# P25_DI_DO.net
KiCad netlist of a schematic drawn in Altium Designer
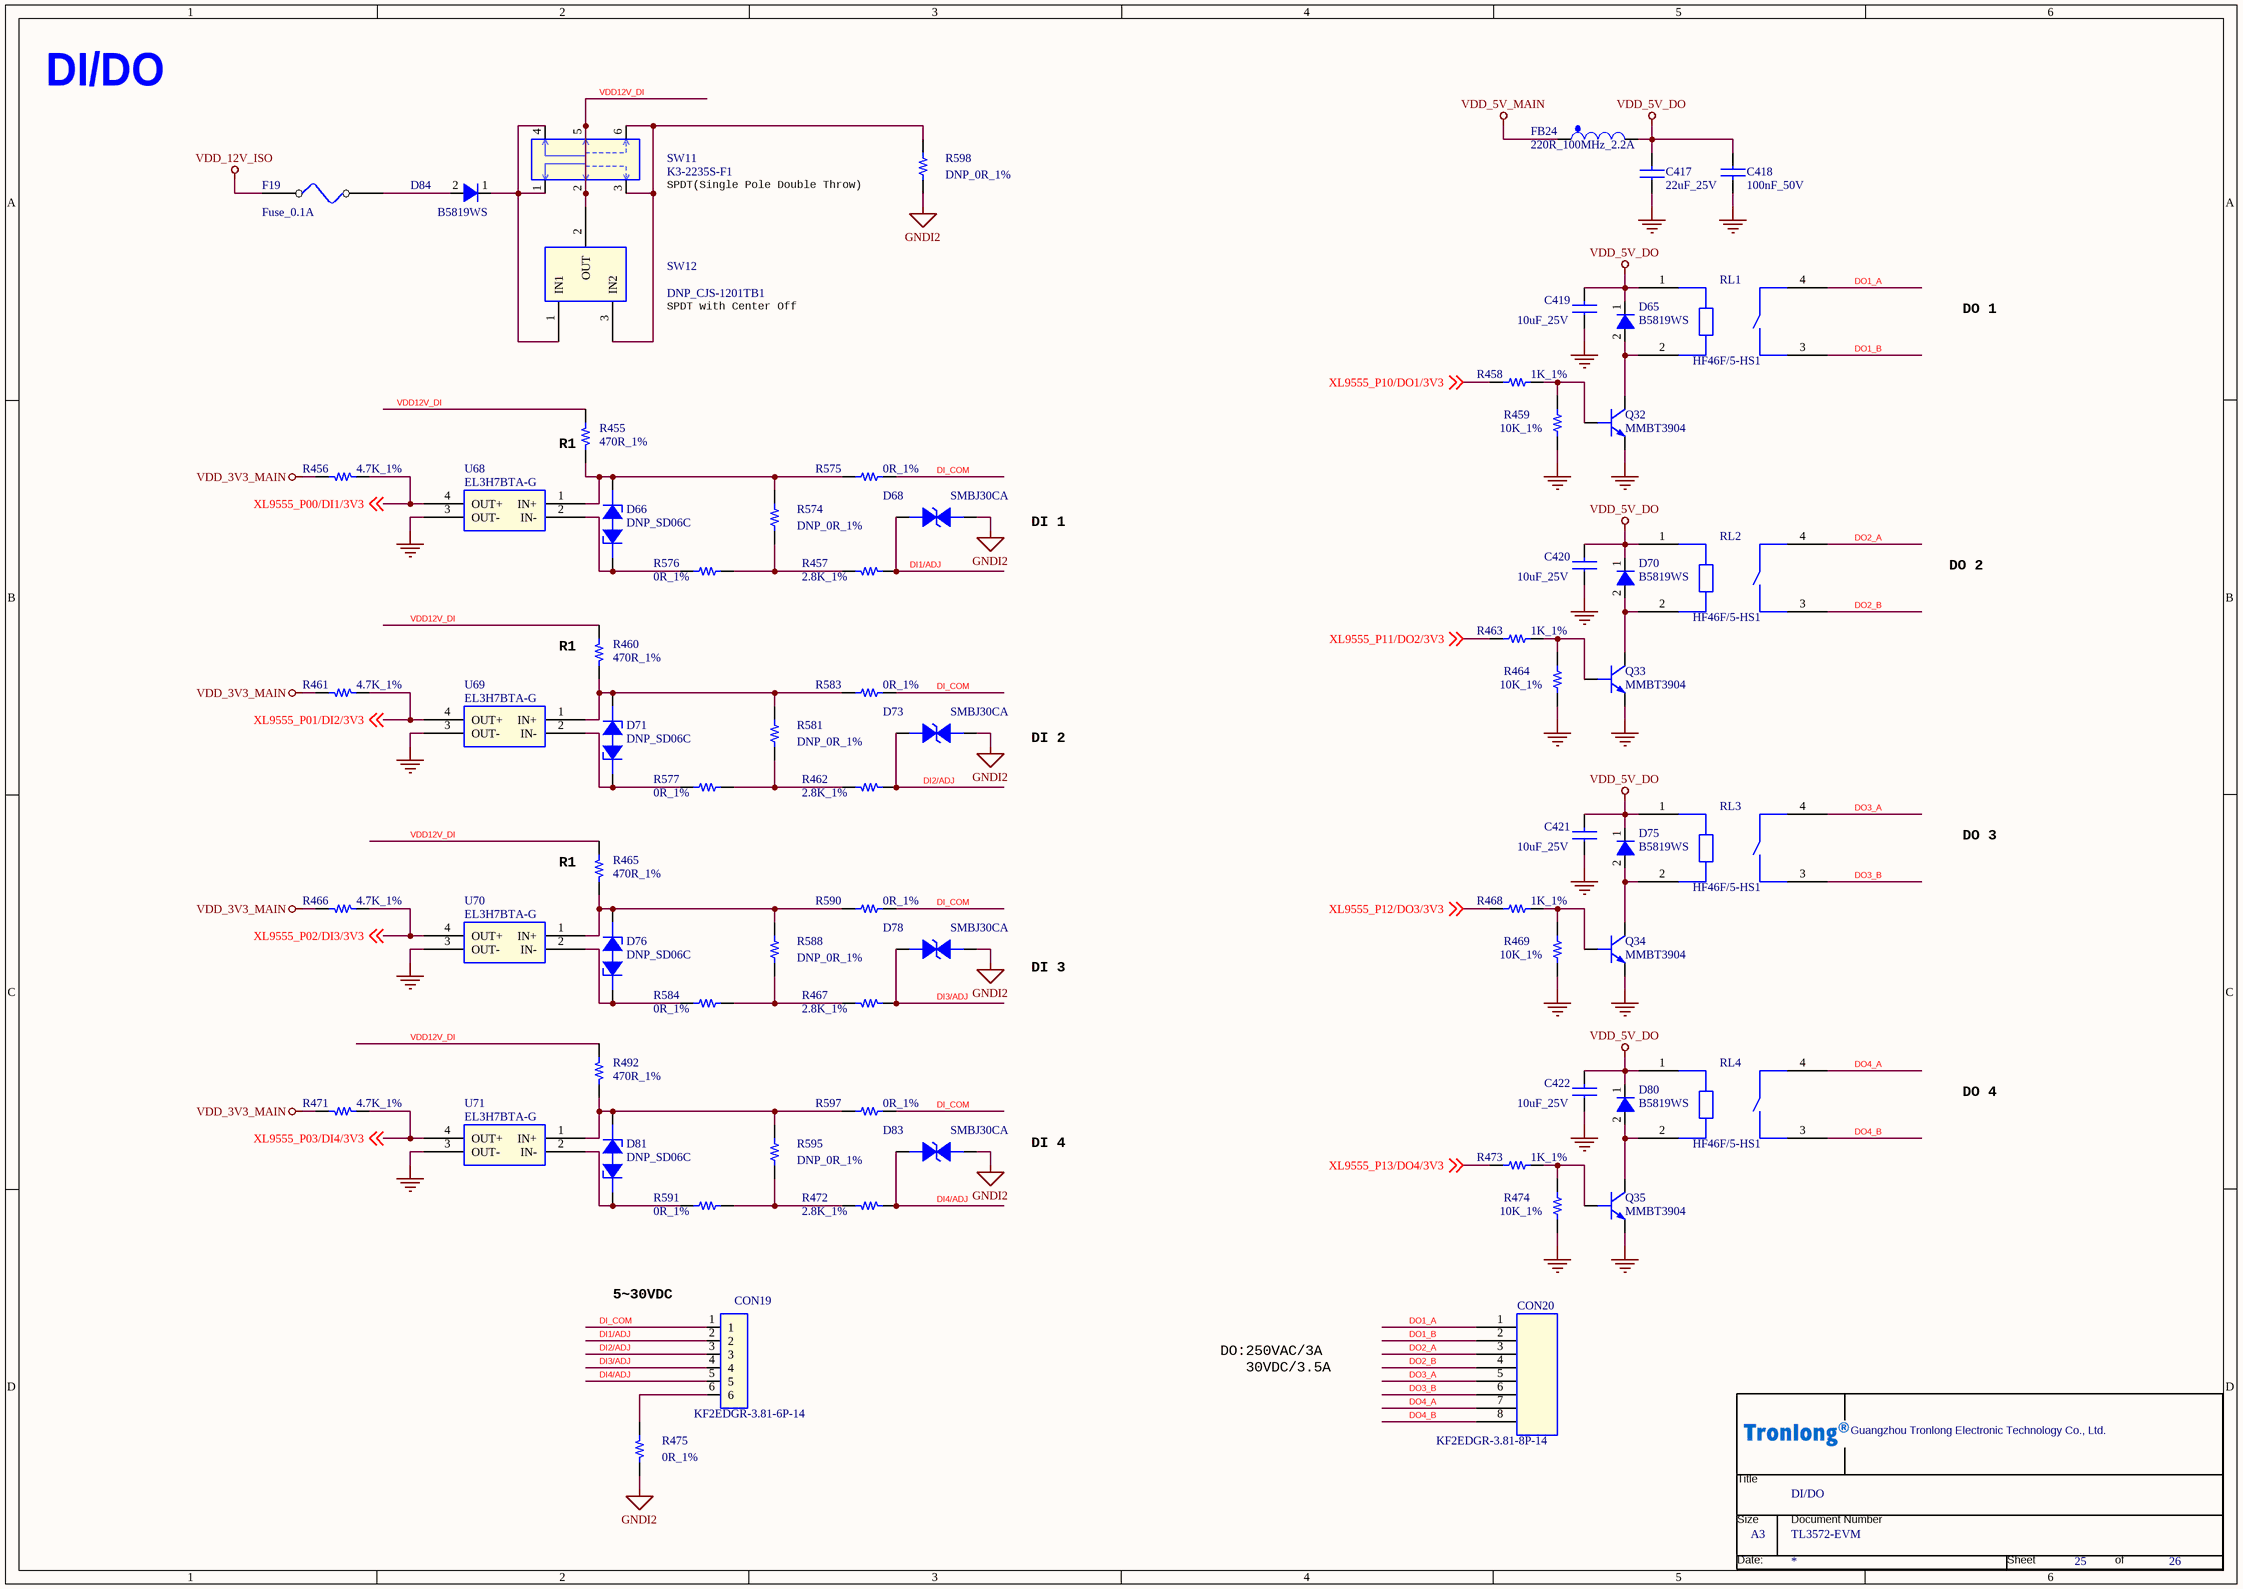
[diagram p0: P25_DI_DO.SchDoc]

(export (version "E")
  (design (tool "Eeschema 10.0.6"))
  (components
    (comp (ref "*")
      (value "TL_NEW")
      (fields
        (field (name "PAGE COUNT") "26")
        (field (name "PAGE NUMBER") "25")
        (field (name "PAGE SIZE") "A3")
        (field (name "ORGNAME") "Guangzhou Tronlong Electronic Technology Co., Ltd.")
        (field (name "TITLE") "DI/DO")
        (field (name "DOC") "TL3572-EVM")
      )
      (libsource (lib "*") (part "TL_NEW"))
    )
    (comp (ref "C417")
      (value "22uF_25V")
      (footprint "C0805")
      (description "贴片陶瓷电容,22uF,20%,25V,X5R")
      (fields
        (field (name "MANUFACTURER") "广东风华高新科技股份有限公司（FH）")
        (field (name "MANUFACTURER PARTNUMBER") "0805X226M250NT")
      )
      (libsource (lib "*") (part "CAP NP_Dup1"))
    )
    (comp (ref "C418")
      (value "100nF_50V")
      (footprint "C0402")
      (description "贴片陶瓷电容,100nF,10%,50V,X7R")
      (fields
        (field (name "MANUFACTURER") "广东风华高新科技股份有限公司（FH）")
        (field (name "MANUFACTURER PARTNUMBER") "0402B104K500NT")
      )
      (libsource (lib "*") (part "CAP NP_Dup1"))
    )
    (comp (ref "C419")
      (value "10uF_25V")
      (footprint "C0603")
      (description "贴片陶瓷电容10uF,20%,25V,X5R")
      (fields
        (field (name "MANUFACTURER PARTNUMBER") "0603X106M250NT")
        (field (name "MANUFACTURER") "广东风华高新科技股份有限公司（FH）")
      )
      (libsource (lib "*") (part "CAP NP_Dup2"))
    )
    (comp (ref "C420")
      (value "10uF_25V")
      (footprint "C0603")
      (description "贴片陶瓷电容10uF,20%,25V,X5R")
      (fields
        (field (name "MANUFACTURER PARTNUMBER") "0603X106M250NT")
        (field (name "MANUFACTURER") "广东风华高新科技股份有限公司（FH）")
      )
      (libsource (lib "*") (part "CAP NP_Dup2"))
    )
    (comp (ref "C421")
      (value "10uF_25V")
      (footprint "C0603")
      (description "贴片陶瓷电容10uF,20%,25V,X5R")
      (fields
        (field (name "MANUFACTURER") "广东风华高新科技股份有限公司（FH）")
        (field (name "MANUFACTURER PARTNUMBER") "0603X106M250NT")
      )
      (libsource (lib "*") (part "CAP NP_Dup2"))
    )
    (comp (ref "C422")
      (value "10uF_25V")
      (footprint "C0603")
      (description "贴片陶瓷电容10uF,20%,25V,X5R")
      (fields
        (field (name "MANUFACTURER") "广东风华高新科技股份有限公司（FH）")
        (field (name "MANUFACTURER PARTNUMBER") "0603X106M250NT")
      )
      (libsource (lib "*") (part "CAP NP_Dup2"))
    )
    (comp (ref "CON19")
      (value "KF2EDGR-3.81-6P-14")
      (footprint "kf2eg_3_81-6p")
      (description "插拔式端子座,1x6P,3.81mm,90度")
      (fields (field (name "MANUFACTURER") "慈溪市科发电子有限公司（KEFA）"))
      (libsource (lib "*") (part "CON6"))
    )
    (comp (ref "CON20")
      (value "KF2EDGR-3.81-8P-14")
      (footprint "CON_KF2EDGR-3R81-8P-14_90_DIP")
      (description "插拔式端子座,1x8P,3.81mm,90度")
      (fields (field (name "MANUFACTURER") "慈溪市科发电子有限公司（KEFA）"))
      (libsource (lib "*") (part "CON8_1"))
    )
    (comp (ref "D65")
      (value "B5819WS")
      (footprint "SOD-323")
      (description "肖特基二极管,VR=40V,IF=1A,VF=0.6V@1A")
      (fields (field (name "MFR") "On Semiconductor") (field (name "TIINTPARTNUMBER") "1E0013"))
      (libsource (lib "*") (part "Diode200mA250V_2"))
    )
    (comp (ref "D66")
      (value "DNP_SD06C")
      (footprint "SOD323")
      (description "TVS二极管,VRWM=6V,VBR=6.5V,一组,双向,30KV,30KV")
      (fields
        (field (name "MANUFACTURER") "上海雷卯电子科技有限公司（Leiditech）")
        (field (name "MANUFACTURER PARTNUMBER") "SD06C")
      )
      (libsource (lib "*") (part "DIODE BREAKDOWN_2"))
    )
    (comp (ref "D68")
      (value "SMBJ30CA")
      (footprint "SMB")
      (description "TVS二极管,VRWM=30V,VBR=33.3V,一组,双向")
      (fields (field (name "MANUFACTURER") "江苏长晶科技有限公司（JSCJ）"))
      (libsource (lib "*") (part "DIODE-TRIG"))
    )
    (comp (ref "D70")
      (value "B5819WS")
      (footprint "SOD-323")
      (description "肖特基二极管,VR=40V,IF=1A,VF=0.6V@1A")
      (fields (field (name "MFR") "On Semiconductor") (field (name "TIINTPARTNUMBER") "1E0013"))
      (libsource (lib "*") (part "Diode200mA250V_2"))
    )
    (comp (ref "D71")
      (value "DNP_SD06C")
      (footprint "SOD323")
      (description "TVS二极管,VRWM=6V,VBR=6.5V,一组,双向,30KV,30KV")
      (fields
        (field (name "MANUFACTURER") "上海雷卯电子科技有限公司（Leiditech）")
        (field (name "MANUFACTURER PARTNUMBER") "SD06C")
      )
      (libsource (lib "*") (part "DIODE BREAKDOWN_2"))
    )
    (comp (ref "D73")
      (value "SMBJ30CA")
      (footprint "SMB")
      (description "TVS二极管,VRWM=30V,VBR=33.3V,一组,双向")
      (fields (field (name "MANUFACTURER") "江苏长晶科技有限公司（JSCJ）"))
      (libsource (lib "*") (part "DIODE-TRIG"))
    )
    (comp (ref "D75")
      (value "B5819WS")
      (footprint "SOD-323")
      (description "肖特基二极管,VR=40V,IF=1A,VF=0.6V@1A")
      (fields (field (name "MFR") "On Semiconductor") (field (name "TIINTPARTNUMBER") "1E0013"))
      (libsource (lib "*") (part "Diode200mA250V_2"))
    )
    (comp (ref "D76")
      (value "DNP_SD06C")
      (footprint "SOD323")
      (description "TVS二极管,VRWM=6V,VBR=6.5V,一组,双向,30KV,30KV")
      (fields
        (field (name "MANUFACTURER") "上海雷卯电子科技有限公司（Leiditech）")
        (field (name "MANUFACTURER PARTNUMBER") "SD06C")
      )
      (libsource (lib "*") (part "DIODE BREAKDOWN_2"))
    )
    (comp (ref "D78")
      (value "SMBJ30CA")
      (footprint "SMB")
      (description "TVS二极管,VRWM=30V,VBR=33.3V,一组,双向")
      (fields (field (name "MANUFACTURER") "江苏长晶科技有限公司（JSCJ）"))
      (libsource (lib "*") (part "DIODE-TRIG"))
    )
    (comp (ref "D80")
      (value "B5819WS")
      (footprint "SOD-323")
      (description "肖特基二极管,VR=40V,IF=1A,VF=0.6V@1A")
      (fields (field (name "MFR") "On Semiconductor") (field (name "TIINTPARTNUMBER") "1E0013"))
      (libsource (lib "*") (part "Diode200mA250V_2"))
    )
    (comp (ref "D81")
      (value "DNP_SD06C")
      (footprint "SOD323")
      (description "TVS二极管,VRWM=6V,VBR=6.5V,一组,双向,30KV,30KV")
      (fields
        (field (name "MANUFACTURER") "上海雷卯电子科技有限公司（Leiditech）")
        (field (name "MANUFACTURER PARTNUMBER") "SD06C")
      )
      (libsource (lib "*") (part "DIODE BREAKDOWN_2"))
    )
    (comp (ref "D83")
      (value "SMBJ30CA")
      (footprint "SMB")
      (description "TVS二极管,VRWM=30V,VBR=33.3V,一组,双向")
      (fields (field (name "MANUFACTURER") "江苏长晶科技有限公司（JSCJ）"))
      (libsource (lib "*") (part "DIODE-TRIG"))
    )
    (comp (ref "D84")
      (value "B5819WS")
      (footprint "SOD-323")
      (description "肖特基二极管,VR=40V,IF=1A,VF=0.6V@1A")
      (fields (field (name "TIINTPARTNUMBER") "1E0013") (field (name "MFR") "On Semiconductor"))
      (libsource (lib "*") (part "Diode200mA250V"))
    )
    (comp (ref "F19")
      (value "Fuse_0.1A")
      (footprint "F0805")
      (description "自恢复保险丝,Vmax=24V,Imax=100A,Ihold=0.1A")
      (fields
        (field (name "MANUFACTURER") "东莞市竞沃电子科技有限公司（TLC）")
        (field (name "MANUFACTURER PARTNUMBER") "TLC-PSMD010/24")
      )
      (libsource (lib "*") (part "FUSE"))
    )
    (comp (ref "FB24")
      (value "220R_100MHz_2.2A")
      (footprint "L0603")
      (description "磁珠,50mΩ,2.2A,220R@100MHz")
      (fields
        (field (name "MANUFACTURER PARTNUMBER") "UPZ1608U221-2R2TF")
        (field (name "MANUFACTURER") "深圳顺络电子股份有限公司（Sunlord）")
      )
      (libsource (lib "*") (part "FB_0"))
    )
    (comp (ref "Q32")
      (value "MMBT3904")
      (footprint "SOT23-3_DBZ3")
      (description "BJT,NPN,Vceo=40V,Ic=200mA,fT=300MHz,PD=200mW")
      (fields (field (name "MANUFACTURER") "江苏长晶科技股份有限公司（JSCJ）"))
      (libsource (lib "*") (part "MMBT3904/SOT"))
    )
    (comp (ref "Q33")
      (value "MMBT3904")
      (footprint "SOT23-3_DBZ3")
      (description "BJT,NPN,Vceo=40V,Ic=200mA,fT=300MHz,PD=200mW")
      (fields (field (name "MANUFACTURER") "江苏长晶科技股份有限公司（JSCJ）"))
      (libsource (lib "*") (part "MMBT3904/SOT"))
    )
    (comp (ref "Q34")
      (value "MMBT3904")
      (footprint "SOT23-3_DBZ3")
      (description "BJT,NPN,Vceo=40V,Ic=200mA,fT=300MHz,PD=200mW")
      (fields (field (name "MANUFACTURER") "江苏长晶科技股份有限公司（JSCJ）"))
      (libsource (lib "*") (part "MMBT3904/SOT"))
    )
    (comp (ref "Q35")
      (value "MMBT3904")
      (footprint "SOT23-3_DBZ3")
      (description "BJT,NPN,Vceo=40V,Ic=200mA,fT=300MHz,PD=200mW")
      (fields (field (name "MANUFACTURER") "江苏长晶科技股份有限公司（JSCJ）"))
      (libsource (lib "*") (part "MMBT3904/SOT"))
    )
    (comp (ref "R455")
      (value "470R_1%")
      (footprint "R0603")
      (description "贴片电阻,470R,±1%,1/10W")
      (fields
        (field (name "MANUFACTURER") "广东风华高新科技股份有限公司（FH）")
        (field (name "MANUFACTURER PARTNUMBER") "RS-03K4700FT")
      )
      (libsource (lib "*") (part "Resistor"))
    )
    (comp (ref "R456")
      (value "4.7K_1%")
      (footprint "R0402")
      (description "贴片电阻,4.7K,±1%,1/16W")
      (fields
        (field (name "MANUFACTURER") "广东风华高新科技股份有限公司（FH）")
        (field (name "MANUFACTURER PARTNUMBER") "RC-02K4701FT")
      )
      (libsource (lib "*") (part "Resistor"))
    )
    (comp (ref "R457")
      (value "2.8K_1%")
      (footprint "R0603")
      (description "/")
      (fields
        (field (name "MANUFACTURER PARTNUMBER") "2.8K,±1%,R0603,≥1/10W")
        (field (name "MANUFACTURER") "广州创龙")
      )
      (libsource (lib "*") (part "Resistor"))
    )
    (comp (ref "R458")
      (value "1K_1%")
      (footprint "R0402")
      (description "贴片电阻,1K,±1%,1/16W")
      (fields
        (field (name "MANUFACTURER PARTNUMBER") "RC-02K1001FT")
        (field (name "MANUFACTURER") "广东风华高新科技股份有限公司（FH）")
      )
      (libsource (lib "*") (part "Resistor"))
    )
    (comp (ref "R459")
      (value "10K_1%")
      (footprint "R0402")
      (description "贴片电阻,10K,±1%,1/16W")
      (fields
        (field (name "MANUFACTURER") "广东风华高新科技股份有限公司（FH）")
        (field (name "MANUFACTURER PARTNUMBER") "RC-02K1002FT")
      )
      (libsource (lib "*") (part "Resistor"))
    )
    (comp (ref "R460")
      (value "470R_1%")
      (footprint "R0603")
      (description "贴片电阻,470R,±1%,1/10W")
      (fields
        (field (name "MANUFACTURER PARTNUMBER") "RS-03K4700FT")
        (field (name "MANUFACTURER") "广东风华高新科技股份有限公司（FH）")
      )
      (libsource (lib "*") (part "Resistor"))
    )
    (comp (ref "R461")
      (value "4.7K_1%")
      (footprint "R0402")
      (description "贴片电阻,4.7K,±1%,1/16W")
      (fields
        (field (name "MANUFACTURER PARTNUMBER") "RC-02K4701FT")
        (field (name "MANUFACTURER") "广东风华高新科技股份有限公司（FH）")
      )
      (libsource (lib "*") (part "Resistor"))
    )
    (comp (ref "R462")
      (value "2.8K_1%")
      (footprint "R0603")
      (description "/")
      (fields
        (field (name "MANUFACTURER") "广州创龙")
        (field (name "MANUFACTURER PARTNUMBER") "2.8K,±1%,R0603,≥1/10W")
      )
      (libsource (lib "*") (part "Resistor"))
    )
    (comp (ref "R463")
      (value "1K_1%")
      (footprint "R0402")
      (description "贴片电阻,1K,±1%,1/16W")
      (fields
        (field (name "MANUFACTURER PARTNUMBER") "RC-02K1001FT")
        (field (name "MANUFACTURER") "广东风华高新科技股份有限公司（FH）")
      )
      (libsource (lib "*") (part "Resistor"))
    )
    (comp (ref "R464")
      (value "10K_1%")
      (footprint "R0402")
      (description "贴片电阻,10K,±1%,1/16W")
      (fields
        (field (name "MANUFACTURER") "广东风华高新科技股份有限公司（FH）")
        (field (name "MANUFACTURER PARTNUMBER") "RC-02K1002FT")
      )
      (libsource (lib "*") (part "Resistor"))
    )
    (comp (ref "R465")
      (value "470R_1%")
      (footprint "R0603")
      (description "贴片电阻,470R,±1%,1/10W")
      (fields
        (field (name "MANUFACTURER PARTNUMBER") "RS-03K4700FT")
        (field (name "MANUFACTURER") "广东风华高新科技股份有限公司（FH）")
      )
      (libsource (lib "*") (part "Resistor"))
    )
    (comp (ref "R466")
      (value "4.7K_1%")
      (footprint "R0402")
      (description "贴片电阻,4.7K,±1%,1/16W")
      (fields
        (field (name "MANUFACTURER PARTNUMBER") "RC-02K4701FT")
        (field (name "MANUFACTURER") "广东风华高新科技股份有限公司（FH）")
      )
      (libsource (lib "*") (part "Resistor"))
    )
    (comp (ref "R467")
      (value "2.8K_1%")
      (footprint "R0603")
      (description "/")
      (fields
        (field (name "MANUFACTURER") "广州创龙")
        (field (name "MANUFACTURER PARTNUMBER") "2.8K,±1%,R0603,≥1/10W")
      )
      (libsource (lib "*") (part "Resistor"))
    )
    (comp (ref "R468")
      (value "1K_1%")
      (footprint "R0402")
      (description "贴片电阻,1K,±1%,1/16W")
      (fields
        (field (name "MANUFACTURER") "广东风华高新科技股份有限公司（FH）")
        (field (name "MANUFACTURER PARTNUMBER") "RC-02K1001FT")
      )
      (libsource (lib "*") (part "Resistor"))
    )
    (comp (ref "R469")
      (value "10K_1%")
      (footprint "R0402")
      (description "贴片电阻,10K,±1%,1/16W")
      (fields
        (field (name "MANUFACTURER PARTNUMBER") "RC-02K1002FT")
        (field (name "MANUFACTURER") "广东风华高新科技股份有限公司（FH）")
      )
      (libsource (lib "*") (part "Resistor"))
    )
    (comp (ref "R471")
      (value "4.7K_1%")
      (footprint "R0402")
      (description "贴片电阻,4.7K,±1%,1/16W")
      (fields
        (field (name "MANUFACTURER PARTNUMBER") "RC-02K4701FT")
        (field (name "MANUFACTURER") "广东风华高新科技股份有限公司（FH）")
      )
      (libsource (lib "*") (part "Resistor"))
    )
    (comp (ref "R472")
      (value "2.8K_1%")
      (footprint "R0603")
      (description "/")
      (fields
        (field (name "MANUFACTURER") "广州创龙")
        (field (name "MANUFACTURER PARTNUMBER") "2.8K,±1%,R0603,≥1/10W")
      )
      (libsource (lib "*") (part "Resistor"))
    )
    (comp (ref "R473")
      (value "1K_1%")
      (footprint "R0402")
      (description "贴片电阻,1K,±1%,1/16W")
      (fields
        (field (name "MANUFACTURER") "广东风华高新科技股份有限公司（FH）")
        (field (name "MANUFACTURER PARTNUMBER") "RC-02K1001FT")
      )
      (libsource (lib "*") (part "Resistor"))
    )
    (comp (ref "R474")
      (value "10K_1%")
      (footprint "R0402")
      (description "贴片电阻,10K,±1%,1/16W")
      (fields
        (field (name "MANUFACTURER PARTNUMBER") "RC-02K1002FT")
        (field (name "MANUFACTURER") "广东风华高新科技股份有限公司（FH）")
      )
      (libsource (lib "*") (part "Resistor"))
    )
    (comp (ref "R475")
      (value "0R_1%")
      (footprint "R0603")
      (description "贴片电阻,0R,±1%,1/8W")
      (fields
        (field (name "MANUFACTURER PARTNUMBER") "RC-03000FT")
        (field (name "MANUFACTURER") "广东风华高新科技股份有限公司（FH）")
      )
      (libsource (lib "*") (part "Resistor"))
    )
    (comp (ref "R492")
      (value "470R_1%")
      (footprint "R0603")
      (description "贴片电阻,470R,±1%,1/10W")
      (fields
        (field (name "MANUFACTURER PARTNUMBER") "RS-03K4700FT")
        (field (name "MANUFACTURER") "广东风华高新科技股份有限公司（FH）")
      )
      (libsource (lib "*") (part "Resistor"))
    )
    (comp (ref "R574")
      (value "DNP_0R_1%")
      (footprint "R0402")
      (description "贴片电阻,0R,±1%,1/16W")
      (fields
        (field (name "MANUFACTURER PARTNUMBER") "RC-02000FT")
        (field (name "MANUFACTURER") "广东风华高新科技股份有限公司（FH）")
      )
      (libsource (lib "*") (part "Resistor_Dup3"))
    )
    (comp (ref "R575")
      (value "0R_1%")
      (footprint "R0402")
      (description "贴片电阻,0R,±1%,1/16W")
      (fields
        (field (name "MANUFACTURER PARTNUMBER") "RC-02000FT")
        (field (name "MANUFACTURER") "广东风华高新科技股份有限公司（FH）")
      )
      (libsource (lib "*") (part "Resistor_Dup3"))
    )
    (comp (ref "R576")
      (value "0R_1%")
      (footprint "R0402")
      (description "贴片电阻,0R,±1%,1/16W")
      (fields
        (field (name "MANUFACTURER PARTNUMBER") "RC-02000FT")
        (field (name "MANUFACTURER") "广东风华高新科技股份有限公司（FH）")
      )
      (libsource (lib "*") (part "Resistor_Dup3"))
    )
    (comp (ref "R577")
      (value "0R_1%")
      (footprint "R0402")
      (description "贴片电阻,0R,±1%,1/16W")
      (fields
        (field (name "MANUFACTURER PARTNUMBER") "RC-02000FT")
        (field (name "MANUFACTURER") "广东风华高新科技股份有限公司（FH）")
      )
      (libsource (lib "*") (part "Resistor_Dup3"))
    )
    (comp (ref "R581")
      (value "DNP_0R_1%")
      (footprint "R0402")
      (description "贴片电阻,0R,±1%,1/16W")
      (fields
        (field (name "MANUFACTURER PARTNUMBER") "RC-02000FT")
        (field (name "MANUFACTURER") "广东风华高新科技股份有限公司（FH）")
      )
      (libsource (lib "*") (part "Resistor_Dup3"))
    )
    (comp (ref "R583")
      (value "0R_1%")
      (footprint "R0402")
      (description "贴片电阻,0R,±1%,1/16W")
      (fields
        (field (name "MANUFACTURER PARTNUMBER") "RC-02000FT")
        (field (name "MANUFACTURER") "广东风华高新科技股份有限公司（FH）")
      )
      (libsource (lib "*") (part "Resistor_Dup3"))
    )
    (comp (ref "R584")
      (value "0R_1%")
      (footprint "R0402")
      (description "贴片电阻,0R,±1%,1/16W")
      (fields
        (field (name "MANUFACTURER PARTNUMBER") "RC-02000FT")
        (field (name "MANUFACTURER") "广东风华高新科技股份有限公司（FH）")
      )
      (libsource (lib "*") (part "Resistor_Dup3"))
    )
    (comp (ref "R588")
      (value "DNP_0R_1%")
      (footprint "R0402")
      (description "贴片电阻,0R,±1%,1/16W")
      (fields
        (field (name "MANUFACTURER PARTNUMBER") "RC-02000FT")
        (field (name "MANUFACTURER") "广东风华高新科技股份有限公司（FH）")
      )
      (libsource (lib "*") (part "Resistor_Dup3"))
    )
    (comp (ref "R590")
      (value "0R_1%")
      (footprint "R0402")
      (description "贴片电阻,0R,±1%,1/16W")
      (fields
        (field (name "MANUFACTURER PARTNUMBER") "RC-02000FT")
        (field (name "MANUFACTURER") "广东风华高新科技股份有限公司（FH）")
      )
      (libsource (lib "*") (part "Resistor_Dup3"))
    )
    (comp (ref "R591")
      (value "0R_1%")
      (footprint "R0402")
      (description "贴片电阻,0R,±1%,1/16W")
      (fields
        (field (name "MANUFACTURER PARTNUMBER") "RC-02000FT")
        (field (name "MANUFACTURER") "广东风华高新科技股份有限公司（FH）")
      )
      (libsource (lib "*") (part "Resistor_Dup3"))
    )
    (comp (ref "R595")
      (value "DNP_0R_1%")
      (footprint "R0402")
      (description "贴片电阻,0R,±1%,1/16W")
      (fields
        (field (name "MANUFACTURER") "广东风华高新科技股份有限公司（FH）")
        (field (name "MANUFACTURER PARTNUMBER") "RC-02000FT")
      )
      (libsource (lib "*") (part "Resistor_Dup3"))
    )
    (comp (ref "R597")
      (value "0R_1%")
      (footprint "R0402")
      (description "贴片电阻,0R,±1%,1/16W")
      (fields
        (field (name "MANUFACTURER PARTNUMBER") "RC-02000FT")
        (field (name "MANUFACTURER") "广东风华高新科技股份有限公司（FH）")
      )
      (libsource (lib "*") (part "Resistor_Dup3"))
    )
    (comp (ref "R598")
      (value "DNP_0R_1%")
      (footprint "R1206")
      (description "贴片电阻,0R,±1%,1/4W")
      (fields
        (field (name "MANUFACTURER") "广东风华高新科技股份有限公司（FH）")
        (field (name "MANUFACTURER PARTNUMBER") "RS-06000FT")
      )
      (libsource (lib "*") (part "Resistor_Dup3"))
    )
    (comp (ref "RL1")
      (value "HF46F/5-HS1")
      (footprint "RTL_HF46F-5-HS1")
      (description "继电器,5V,一组转换,单刀单掷,5A")
      (fields (field (name "MANUFACTURER") "厦门宏发电声股份有限公司(HONGFA)"))
      (libsource (lib "*") (part "RTL_HF46F-5-HS1"))
    )
    (comp (ref "RL2")
      (value "HF46F/5-HS1")
      (footprint "RTL_HF46F-5-HS1")
      (description "继电器,5V,一组转换,单刀单掷,5A")
      (fields (field (name "MANUFACTURER") "厦门宏发电声股份有限公司(HONGFA)"))
      (libsource (lib "*") (part "RTL_HF46F-5-HS1"))
    )
    (comp (ref "RL3")
      (value "HF46F/5-HS1")
      (footprint "RTL_HF46F-5-HS1")
      (description "继电器,5V,一组转换,单刀单掷,5A")
      (fields (field (name "MANUFACTURER") "厦门宏发电声股份有限公司(HONGFA)"))
      (libsource (lib "*") (part "RTL_HF46F-5-HS1"))
    )
    (comp (ref "RL4")
      (value "HF46F/5-HS1")
      (footprint "RTL_HF46F-5-HS1")
      (description "继电器,5V,一组转换,单刀单掷,5A")
      (fields (field (name "MANUFACTURER") "厦门宏发电声股份有限公司(HONGFA)"))
      (libsource (lib "*") (part "RTL_HF46F-5-HS1"))
    )
    (comp (ref "SW11")
      (value "K3-2235S-F1")
      (footprint "SW-6P-L9169P2D5-SMD")
      (description "贴片拨动开关,2P2T,180,黑色,无定位柱")
      (fields (field (name "MANUFACTURER") "HRO(韩国韩荣)"))
      (libsource (lib "*") (part "SW_2P2T"))
    )
    (comp (ref "SW12")
      (value "DNP_CJS-1201TB1")
      (footprint "SW_SMD_3P_L60W25_P350_LS42")
      (fields
        (field (name "LPD_PART_NUMBER") "1012777")
        (field (name "MFR_PART_NUMBER") "S3M24.576B20F30TNN")
      )
      (libsource (lib "*") (part "CMX309_1"))
    )
    (comp (ref "U68")
      (value "EL3H7BTA-G")
      (footprint "soic127p700x200-4n")
      (description "光耦,VF=1.2V,IF=50mA,IO=50mA,VCEO=80V,1通道")
      (fields (field (name "MANUFACTURER") "EVERLIGHT(台湾亿光电子工业股份有限公司)"))
      (libsource (lib "*") (part "PC817"))
    )
    (comp (ref "U69")
      (value "EL3H7BTA-G")
      (footprint "soic127p700x200-4n")
      (description "光耦,VF=1.2V,IF=50mA,IO=50mA,VCEO=80V,1通道")
      (fields (field (name "MANUFACTURER") "EVERLIGHT(台湾亿光电子工业股份有限公司)"))
      (libsource (lib "*") (part "PC817"))
    )
    (comp (ref "U70")
      (value "EL3H7BTA-G")
      (footprint "soic127p700x200-4n")
      (description "光耦,VF=1.2V,IF=50mA,IO=50mA,VCEO=80V,1通道")
      (fields (field (name "MANUFACTURER") "EVERLIGHT(台湾亿光电子工业股份有限公司)"))
      (libsource (lib "*") (part "PC817"))
    )
    (comp (ref "U71")
      (value "EL3H7BTA-G")
      (footprint "soic127p700x200-4n")
      (description "光耦,VF=1.2V,IF=50mA,IO=50mA,VCEO=80V,1通道")
      (fields (field (name "MANUFACTURER") "EVERLIGHT(台湾亿光电子工业股份有限公司)"))
      (libsource (lib "*") (part "PC817"))
    )
  )
  (nets
    (net (code "1") (name "/DI1{slash}ADJ") (class "Default")
      (node (ref "CON19") (pin "2") (pinfunction "2_2") (pintype "passive"))
      (node (ref "D68") (pin "2") (pinfunction "2_2") (pintype "passive"))
      (node (ref "R457") (pin "2") (pinfunction "2_2") (pintype "passive"))
    )
    (net (code "2") (name "/DI2{slash}ADJ") (class "Default")
      (node (ref "CON19") (pin "3") (pinfunction "3_3") (pintype "passive"))
      (node (ref "D73") (pin "2") (pinfunction "2_2") (pintype "passive"))
      (node (ref "R462") (pin "2") (pinfunction "2_2") (pintype "passive"))
    )
    (net (code "3") (name "/DI3{slash}ADJ") (class "Default")
      (node (ref "CON19") (pin "4") (pinfunction "4_4") (pintype "passive"))
      (node (ref "D78") (pin "2") (pinfunction "2_2") (pintype "passive"))
      (node (ref "R467") (pin "2") (pinfunction "2_2") (pintype "passive"))
    )
    (net (code "4") (name "/DI4{slash}ADJ") (class "Default")
      (node (ref "CON19") (pin "5") (pinfunction "5_5") (pintype "passive"))
      (node (ref "D83") (pin "2") (pinfunction "2_2") (pintype "passive"))
      (node (ref "R472") (pin "2") (pinfunction "2_2") (pintype "passive"))
    )
    (net (code "5") (name "/DI_COM") (class "Default")
      (node (ref "CON19") (pin "1") (pinfunction "1_1") (pintype "passive"))
      (node (ref "R575") (pin "2") (pinfunction "2_2") (pintype "passive"))
      (node (ref "R583") (pin "2") (pinfunction "2_2") (pintype "passive"))
      (node (ref "R590") (pin "2") (pinfunction "2_2") (pintype "passive"))
      (node (ref "R597") (pin "2") (pinfunction "2_2") (pintype "passive"))
    )
    (net (code "6") (name "/DO1_A") (class "Default")
      (node (ref "CON20") (pin "1") (pinfunction "1_1") (pintype "passive"))
      (node (ref "RL1") (pin "4") (pinfunction "4_4") (pintype "passive"))
    )
    (net (code "7") (name "/DO1_B") (class "Default")
      (node (ref "CON20") (pin "2") (pinfunction "2_2") (pintype "passive"))
      (node (ref "RL1") (pin "3") (pinfunction "3_3") (pintype "passive"))
    )
    (net (code "8") (name "/DO2_A") (class "Default")
      (node (ref "CON20") (pin "3") (pinfunction "3_3") (pintype "passive"))
      (node (ref "RL2") (pin "4") (pinfunction "4_4") (pintype "passive"))
    )
    (net (code "9") (name "/DO2_B") (class "Default")
      (node (ref "CON20") (pin "4") (pinfunction "4_4") (pintype "passive"))
      (node (ref "RL2") (pin "3") (pinfunction "3_3") (pintype "passive"))
    )
    (net (code "10") (name "/DO3_A") (class "Default")
      (node (ref "CON20") (pin "5") (pinfunction "5_5") (pintype "passive"))
      (node (ref "RL3") (pin "4") (pinfunction "4_4") (pintype "passive"))
    )
    (net (code "11") (name "/DO3_B") (class "Default")
      (node (ref "CON20") (pin "6") (pinfunction "6_6") (pintype "passive"))
      (node (ref "RL3") (pin "3") (pinfunction "3_3") (pintype "passive"))
    )
    (net (code "12") (name "/DO4_A") (class "Default")
      (node (ref "CON20") (pin "7") (pinfunction "7_7") (pintype "passive"))
      (node (ref "RL4") (pin "4") (pinfunction "4_4") (pintype "passive"))
    )
    (net (code "13") (name "/DO4_B") (class "Default")
      (node (ref "CON20") (pin "8") (pinfunction "8_8") (pintype "passive"))
      (node (ref "RL4") (pin "3") (pinfunction "3_3") (pintype "passive"))
    )
    (net (code "14") (name "/VDD12V_DI") (class "Default")
      (node (ref "R455") (pin "1") (pinfunction "1_1") (pintype "passive"))
      (node (ref "R460") (pin "1") (pinfunction "1_1") (pintype "passive"))
      (node (ref "R465") (pin "1") (pinfunction "1_1") (pintype "passive"))
      (node (ref "R492") (pin "1") (pinfunction "1_1") (pintype "passive"))
      (node (ref "SW11") (pin "2") (pinfunction "2_2") (pintype "passive"))
      (node (ref "SW11") (pin "5") (pinfunction "5_5") (pintype "passive"))
      (node (ref "SW12") (pin "2") (pinfunction "OUT_2") (pintype "passive"))
    )
    (net (code "15") (name "GND") (class "Default")
      (node (ref "C417") (pin "1") (pinfunction "1_1") (pintype "passive"))
      (node (ref "C418") (pin "2") (pinfunction "2_2") (pintype "passive"))
      (node (ref "C419") (pin "1") (pinfunction "1_1") (pintype "passive"))
      (node (ref "C420") (pin "1") (pinfunction "1_1") (pintype "passive"))
      (node (ref "C421") (pin "1") (pinfunction "1_1") (pintype "passive"))
      (node (ref "C422") (pin "1") (pinfunction "1_1") (pintype "passive"))
      (node (ref "Q32") (pin "2") (pinfunction "E_2") (pintype "passive"))
      (node (ref "Q33") (pin "2") (pinfunction "E_2") (pintype "passive"))
      (node (ref "Q34") (pin "2") (pinfunction "E_2") (pintype "passive"))
      (node (ref "Q35") (pin "2") (pinfunction "E_2") (pintype "passive"))
      (node (ref "R459") (pin "2") (pinfunction "2_2") (pintype "passive"))
      (node (ref "R464") (pin "2") (pinfunction "2_2") (pintype "passive"))
      (node (ref "R469") (pin "2") (pinfunction "2_2") (pintype "passive"))
      (node (ref "R474") (pin "2") (pinfunction "2_2") (pintype "passive"))
      (node (ref "U68") (pin "3") (pinfunction "OUT-_3") (pintype "passive"))
      (node (ref "U69") (pin "3") (pinfunction "OUT-_3") (pintype "passive"))
      (node (ref "U70") (pin "3") (pinfunction "OUT-_3") (pintype "passive"))
      (node (ref "U71") (pin "3") (pinfunction "OUT-_3") (pintype "passive"))
    )
    (net (code "16") (name "GNDI2") (class "Default")
      (node (ref "D68") (pin "1") (pinfunction "1_1") (pintype "passive"))
      (node (ref "D73") (pin "1") (pinfunction "1_1") (pintype "passive"))
      (node (ref "D78") (pin "1") (pinfunction "1_1") (pintype "passive"))
      (node (ref "D83") (pin "1") (pinfunction "1_1") (pintype "passive"))
      (node (ref "R475") (pin "2") (pinfunction "2_2") (pintype "passive"))
      (node (ref "R598") (pin "1") (pinfunction "1_1") (pintype "passive"))
    )
    (net (code "17") (name "Net-(CON19-Pad6)") (class "Default")
      (node (ref "CON19") (pin "6") (pinfunction "6_6") (pintype "passive"))
      (node (ref "R475") (pin "1") (pinfunction "1_1") (pintype "passive"))
    )
    (net (code "18") (name "Net-(D65-Cathode)") (class "Default")
      (node (ref "D65") (pin "2") (pinfunction "Cathode_2") (pintype "passive"))
      (node (ref "Q32") (pin "3") (pinfunction "C_3") (pintype "passive"))
      (node (ref "RL1") (pin "2") (pinfunction "2_2") (pintype "passive"))
    )
    (net (code "19") (name "Net-(D66-ANODE1)") (class "Default")
      (node (ref "D66") (pin "1") (pinfunction "ANODE1_1") (pintype "passive"))
      (node (ref "R455") (pin "2") (pinfunction "2_2") (pintype "passive"))
      (node (ref "R574") (pin "1") (pinfunction "1_1") (pintype "passive"))
      (node (ref "R575") (pin "1") (pinfunction "1_1") (pintype "passive"))
      (node (ref "U68") (pin "1") (pinfunction "IN+_1") (pintype "passive"))
    )
    (net (code "20") (name "Net-(D66-CATHODE2)") (class "Default")
      (node (ref "D66") (pin "2") (pinfunction "CATHODE2_2") (pintype "passive"))
      (node (ref "R576") (pin "1") (pinfunction "1_1") (pintype "passive"))
      (node (ref "U68") (pin "2") (pinfunction "IN-_2") (pintype "passive"))
    )
    (net (code "21") (name "Net-(D70-Cathode)") (class "Default")
      (node (ref "D70") (pin "2") (pinfunction "Cathode_2") (pintype "passive"))
      (node (ref "Q33") (pin "3") (pinfunction "C_3") (pintype "passive"))
      (node (ref "RL2") (pin "2") (pinfunction "2_2") (pintype "passive"))
    )
    (net (code "22") (name "Net-(D71-ANODE1)") (class "Default")
      (node (ref "D71") (pin "1") (pinfunction "ANODE1_1") (pintype "passive"))
      (node (ref "R460") (pin "2") (pinfunction "2_2") (pintype "passive"))
      (node (ref "R581") (pin "1") (pinfunction "1_1") (pintype "passive"))
      (node (ref "R583") (pin "1") (pinfunction "1_1") (pintype "passive"))
      (node (ref "U69") (pin "1") (pinfunction "IN+_1") (pintype "passive"))
    )
    (net (code "23") (name "Net-(D71-CATHODE2)") (class "Default")
      (node (ref "D71") (pin "2") (pinfunction "CATHODE2_2") (pintype "passive"))
      (node (ref "R577") (pin "1") (pinfunction "1_1") (pintype "passive"))
      (node (ref "U69") (pin "2") (pinfunction "IN-_2") (pintype "passive"))
    )
    (net (code "24") (name "Net-(D75-Cathode)") (class "Default")
      (node (ref "D75") (pin "2") (pinfunction "Cathode_2") (pintype "passive"))
      (node (ref "Q34") (pin "3") (pinfunction "C_3") (pintype "passive"))
      (node (ref "RL3") (pin "2") (pinfunction "2_2") (pintype "passive"))
    )
    (net (code "25") (name "Net-(D76-ANODE1)") (class "Default")
      (node (ref "D76") (pin "1") (pinfunction "ANODE1_1") (pintype "passive"))
      (node (ref "R465") (pin "2") (pinfunction "2_2") (pintype "passive"))
      (node (ref "R588") (pin "1") (pinfunction "1_1") (pintype "passive"))
      (node (ref "R590") (pin "1") (pinfunction "1_1") (pintype "passive"))
      (node (ref "U70") (pin "1") (pinfunction "IN+_1") (pintype "passive"))
    )
    (net (code "26") (name "Net-(D76-CATHODE2)") (class "Default")
      (node (ref "D76") (pin "2") (pinfunction "CATHODE2_2") (pintype "passive"))
      (node (ref "R584") (pin "1") (pinfunction "1_1") (pintype "passive"))
      (node (ref "U70") (pin "2") (pinfunction "IN-_2") (pintype "passive"))
    )
    (net (code "27") (name "Net-(D80-Cathode)") (class "Default")
      (node (ref "D80") (pin "2") (pinfunction "Cathode_2") (pintype "passive"))
      (node (ref "Q35") (pin "3") (pinfunction "C_3") (pintype "passive"))
      (node (ref "RL4") (pin "2") (pinfunction "2_2") (pintype "passive"))
    )
    (net (code "28") (name "Net-(D81-ANODE1)") (class "Default")
      (node (ref "D81") (pin "1") (pinfunction "ANODE1_1") (pintype "passive"))
      (node (ref "R492") (pin "2") (pinfunction "2_2") (pintype "passive"))
      (node (ref "R595") (pin "1") (pinfunction "1_1") (pintype "passive"))
      (node (ref "R597") (pin "1") (pinfunction "1_1") (pintype "passive"))
      (node (ref "U71") (pin "1") (pinfunction "IN+_1") (pintype "passive"))
    )
    (net (code "29") (name "Net-(D81-CATHODE2)") (class "Default")
      (node (ref "D81") (pin "2") (pinfunction "CATHODE2_2") (pintype "passive"))
      (node (ref "R591") (pin "1") (pinfunction "1_1") (pintype "passive"))
      (node (ref "U71") (pin "2") (pinfunction "IN-_2") (pintype "passive"))
    )
    (net (code "30") (name "Net-(D84-Anode)") (class "Default")
      (node (ref "D84") (pin "2") (pinfunction "Anode_2") (pintype "passive"))
      (node (ref "F19") (pin "2") (pinfunction "2_2") (pintype "passive"))
    )
    (net (code "31") (name "Net-(D84-Cathode)") (class "Default")
      (node (ref "D84") (pin "1") (pinfunction "Cathode_1") (pintype "passive"))
      (node (ref "SW11") (pin "1") (pinfunction "1_1") (pintype "passive"))
      (node (ref "SW11") (pin "4") (pinfunction "4_4") (pintype "passive"))
      (node (ref "SW12") (pin "1") (pinfunction "IN1_1") (pintype "passive"))
    )
    (net (code "32") (name "Net-(Q32-B)") (class "Default")
      (node (ref "Q32") (pin "1") (pinfunction "B_1") (pintype "passive"))
      (node (ref "R458") (pin "1") (pinfunction "1_1") (pintype "passive"))
      (node (ref "R459") (pin "1") (pinfunction "1_1") (pintype "passive"))
    )
    (net (code "33") (name "Net-(Q33-B)") (class "Default")
      (node (ref "Q33") (pin "1") (pinfunction "B_1") (pintype "passive"))
      (node (ref "R463") (pin "1") (pinfunction "1_1") (pintype "passive"))
      (node (ref "R464") (pin "1") (pinfunction "1_1") (pintype "passive"))
    )
    (net (code "34") (name "Net-(Q34-B)") (class "Default")
      (node (ref "Q34") (pin "1") (pinfunction "B_1") (pintype "passive"))
      (node (ref "R468") (pin "1") (pinfunction "1_1") (pintype "passive"))
      (node (ref "R469") (pin "1") (pinfunction "1_1") (pintype "passive"))
    )
    (net (code "35") (name "Net-(Q35-B)") (class "Default")
      (node (ref "Q35") (pin "1") (pinfunction "B_1") (pintype "passive"))
      (node (ref "R473") (pin "1") (pinfunction "1_1") (pintype "passive"))
      (node (ref "R474") (pin "1") (pinfunction "1_1") (pintype "passive"))
    )
    (net (code "36") (name "Net-(R457-Pad1)") (class "Default")
      (node (ref "R457") (pin "1") (pinfunction "1_1") (pintype "passive"))
      (node (ref "R574") (pin "2") (pinfunction "2_2") (pintype "passive"))
      (node (ref "R576") (pin "2") (pinfunction "2_2") (pintype "passive"))
    )
    (net (code "37") (name "Net-(R462-Pad1)") (class "Default")
      (node (ref "R462") (pin "1") (pinfunction "1_1") (pintype "passive"))
      (node (ref "R577") (pin "2") (pinfunction "2_2") (pintype "passive"))
      (node (ref "R581") (pin "2") (pinfunction "2_2") (pintype "passive"))
    )
    (net (code "38") (name "Net-(R467-Pad1)") (class "Default")
      (node (ref "R467") (pin "1") (pinfunction "1_1") (pintype "passive"))
      (node (ref "R584") (pin "2") (pinfunction "2_2") (pintype "passive"))
      (node (ref "R588") (pin "2") (pinfunction "2_2") (pintype "passive"))
    )
    (net (code "39") (name "Net-(R472-Pad1)") (class "Default")
      (node (ref "R472") (pin "1") (pinfunction "1_1") (pintype "passive"))
      (node (ref "R591") (pin "2") (pinfunction "2_2") (pintype "passive"))
      (node (ref "R595") (pin "2") (pinfunction "2_2") (pintype "passive"))
    )
    (net (code "40") (name "Net-(SW12-IN2)") (class "Default")
      (node (ref "R598") (pin "2") (pinfunction "2_2") (pintype "passive"))
      (node (ref "SW11") (pin "3") (pinfunction "3_3") (pintype "passive"))
      (node (ref "SW11") (pin "6") (pinfunction "6_6") (pintype "passive"))
      (node (ref "SW12") (pin "3") (pinfunction "IN2_3") (pintype "passive"))
    )
    (net (code "41") (name "VDD_3V3_MAIN") (class "Default")
      (node (ref "R456") (pin "1") (pinfunction "1_1") (pintype "passive"))
      (node (ref "R461") (pin "1") (pinfunction "1_1") (pintype "passive"))
      (node (ref "R466") (pin "1") (pinfunction "1_1") (pintype "passive"))
      (node (ref "R471") (pin "1") (pinfunction "1_1") (pintype "passive"))
    )
    (net (code "42") (name "VDD_5V_DO") (class "Default")
      (node (ref "C417") (pin "2") (pinfunction "2_2") (pintype "passive"))
      (node (ref "C418") (pin "1") (pinfunction "1_1") (pintype "passive"))
      (node (ref "C419") (pin "2") (pinfunction "2_2") (pintype "passive"))
      (node (ref "C420") (pin "2") (pinfunction "2_2") (pintype "passive"))
      (node (ref "C421") (pin "2") (pinfunction "2_2") (pintype "passive"))
      (node (ref "C422") (pin "2") (pinfunction "2_2") (pintype "passive"))
      (node (ref "D65") (pin "1") (pinfunction "Anode_1") (pintype "passive"))
      (node (ref "D70") (pin "1") (pinfunction "Anode_1") (pintype "passive"))
      (node (ref "D75") (pin "1") (pinfunction "Anode_1") (pintype "passive"))
      (node (ref "D80") (pin "1") (pinfunction "Anode_1") (pintype "passive"))
      (node (ref "FB24") (pin "2") (pinfunction "2_2") (pintype "passive"))
      (node (ref "RL1") (pin "1") (pinfunction "1_1") (pintype "passive"))
      (node (ref "RL2") (pin "1") (pinfunction "1_1") (pintype "passive"))
      (node (ref "RL3") (pin "1") (pinfunction "1_1") (pintype "passive"))
      (node (ref "RL4") (pin "1") (pinfunction "1_1") (pintype "passive"))
    )
    (net (code "43") (name "VDD_5V_MAIN") (class "Default")
      (node (ref "FB24") (pin "1") (pinfunction "1_1") (pintype "passive"))
    )
    (net (code "44") (name "VDD_12V_ISO") (class "Default")
      (node (ref "F19") (pin "1") (pinfunction "1_1") (pintype "passive"))
    )
    (net (code "45") (name "XL9555_P00{slash}DI1{slash}3V3") (class "Default")
      (node (ref "R456") (pin "2") (pinfunction "2_2") (pintype "passive"))
      (node (ref "U68") (pin "4") (pinfunction "OUT+_4") (pintype "passive"))
    )
    (net (code "46") (name "XL9555_P01{slash}DI2{slash}3V3") (class "Default")
      (node (ref "R461") (pin "2") (pinfunction "2_2") (pintype "passive"))
      (node (ref "U69") (pin "4") (pinfunction "OUT+_4") (pintype "passive"))
    )
    (net (code "47") (name "XL9555_P02{slash}DI3{slash}3V3") (class "Default")
      (node (ref "R466") (pin "2") (pinfunction "2_2") (pintype "passive"))
      (node (ref "U70") (pin "4") (pinfunction "OUT+_4") (pintype "passive"))
    )
    (net (code "48") (name "XL9555_P03{slash}DI4{slash}3V3") (class "Default")
      (node (ref "R471") (pin "2") (pinfunction "2_2") (pintype "passive"))
      (node (ref "U71") (pin "4") (pinfunction "OUT+_4") (pintype "passive"))
    )
    (net (code "49") (name "XL9555_P10{slash}DO1{slash}3V3") (class "Default")
      (node (ref "R458") (pin "2") (pinfunction "2_2") (pintype "passive"))
    )
    (net (code "50") (name "XL9555_P11{slash}DO2{slash}3V3") (class "Default")
      (node (ref "R463") (pin "2") (pinfunction "2_2") (pintype "passive"))
    )
    (net (code "51") (name "XL9555_P12{slash}DO3{slash}3V3") (class "Default")
      (node (ref "R468") (pin "2") (pinfunction "2_2") (pintype "passive"))
    )
    (net (code "52") (name "XL9555_P13{slash}DO4{slash}3V3") (class "Default")
      (node (ref "R473") (pin "2") (pinfunction "2_2") (pintype "passive"))
    )
  )
)
